# SEMAFORO.net
KiCad netlist of a schematic drawn in EAGLE
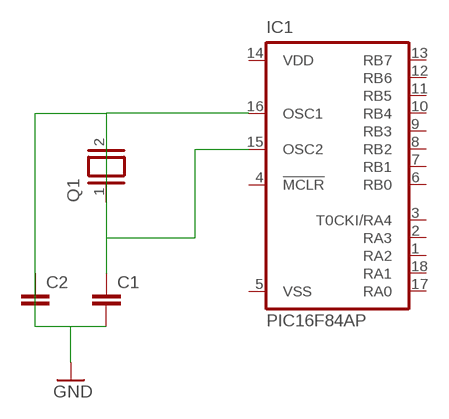
[diagram p0: schematic, sheet 1]

(export (version "E")
  (design (tool "Eeschema 10.0.6"))
  (components
    (comp (ref "C1")
      (value "C2.5/2")
      (footprint "eagle-import:C2.5-2")
      (libsource (lib "eagle-import") (part "C2.5/2"))
    )
    (comp (ref "C2")
      (value "C2.5/2")
      (footprint "eagle-import:C2.5-2")
      (libsource (lib "eagle-import") (part "C2.5/2"))
    )
    (comp (ref "IC1")
      (value "PIC16F84AP")
      (footprint "eagle-import:DIL18")
      (fields (field (name "MF") "MICROCHIP") (field (name "MPN") "PIC16F84A-04I/P"))
      (libsource (lib "eagle-import") (part "PIC16F8P4A"))
    )
    (comp (ref "Q1")
      (value "XTAL/S")
      (footprint "eagle-import:QS")
      (libsource (lib "eagle-import") (part "XTAL/S"))
    )
  )
  (nets
    (net (code "1") (name "/VDD") (class "Default")
      (node (ref "IC1") (pin "14") (pinfunction "VDD_14") (pintype "power_in"))
    )
    (net (code "2") (name "/VSS") (class "Default")
      (node (ref "IC1") (pin "5") (pinfunction "VSS_5") (pintype "power_in"))
    )
    (net (code "3") (name "GND") (class "Default")
      (node (ref "C1") (pin "1") (pinfunction "1_1") (pintype "passive"))
      (node (ref "C1") (pin "2") (pinfunction "2_2") (pintype "passive"))
      (node (ref "C2") (pin "1") (pinfunction "1_1") (pintype "passive"))
      (node (ref "C2") (pin "2") (pinfunction "2_2") (pintype "passive"))
      (node (ref "IC1") (pin "15") (pinfunction "OSC2_15") (pintype "output"))
      (node (ref "IC1") (pin "16") (pinfunction "OSC1_16") (pintype "input"))
      (node (ref "Q1") (pin "1") (pinfunction "1_1") (pintype "passive"))
      (node (ref "Q1") (pin "2") (pinfunction "2_2") (pintype "passive"))
    )
    (net (code "4") (name "unconnected-(IC1-RA0-Pad17)") (class "Default")
      (node (ref "IC1") (pin "17") (pinfunction "RA0_17") (pintype "bidirectional"))
    )
    (net (code "5") (name "unconnected-(IC1-RA1-Pad18)") (class "Default")
      (node (ref "IC1") (pin "18") (pinfunction "RA1_18") (pintype "bidirectional"))
    )
    (net (code "6") (name "unconnected-(IC1-RA2-Pad1)") (class "Default")
      (node (ref "IC1") (pin "1") (pinfunction "RA2_1") (pintype "bidirectional"))
    )
    (net (code "7") (name "unconnected-(IC1-RA3-Pad2)") (class "Default")
      (node (ref "IC1") (pin "2") (pinfunction "RA3_2") (pintype "bidirectional"))
    )
    (net (code "8") (name "unconnected-(IC1-RB0-Pad6)") (class "Default")
      (node (ref "IC1") (pin "6") (pinfunction "RB0_6") (pintype "bidirectional"))
    )
    (net (code "9") (name "unconnected-(IC1-RB1-Pad7)") (class "Default")
      (node (ref "IC1") (pin "7") (pinfunction "RB1_7") (pintype "bidirectional"))
    )
    (net (code "10") (name "unconnected-(IC1-RB2-Pad8)") (class "Default")
      (node (ref "IC1") (pin "8") (pinfunction "RB2_8") (pintype "bidirectional"))
    )
    (net (code "11") (name "unconnected-(IC1-RB3-Pad9)") (class "Default")
      (node (ref "IC1") (pin "9") (pinfunction "RB3_9") (pintype "bidirectional"))
    )
    (net (code "12") (name "unconnected-(IC1-RB4-Pad10)") (class "Default")
      (node (ref "IC1") (pin "10") (pinfunction "RB4_10") (pintype "bidirectional"))
    )
    (net (code "13") (name "unconnected-(IC1-RB5-Pad11)") (class "Default")
      (node (ref "IC1") (pin "11") (pinfunction "RB5_11") (pintype "bidirectional"))
    )
    (net (code "14") (name "unconnected-(IC1-RB6-Pad12)") (class "Default")
      (node (ref "IC1") (pin "12") (pinfunction "RB6_12") (pintype "bidirectional"))
    )
    (net (code "15") (name "unconnected-(IC1-RB7-Pad13)") (class "Default")
      (node (ref "IC1") (pin "13") (pinfunction "RB7_13") (pintype "bidirectional"))
    )
    (net (code "16") (name "unconnected-(IC1-T0CKI{slash}RA4-Pad3)") (class "Default")
      (node (ref "IC1") (pin "3") (pinfunction "T0CKI/RA4_3") (pintype "bidirectional"))
    )
    (net (code "17") (name "unconnected-(IC1-~{MCLR}-Pad4)") (class "Default")
      (node (ref "IC1") (pin "4") (pinfunction "~{MCLR}_4") (pintype "input"))
    )
  )
)
